# JM_Logics_I2C_SMD_Adapter_v0_1.net
KiCad netlist of a schematic drawn in EAGLE
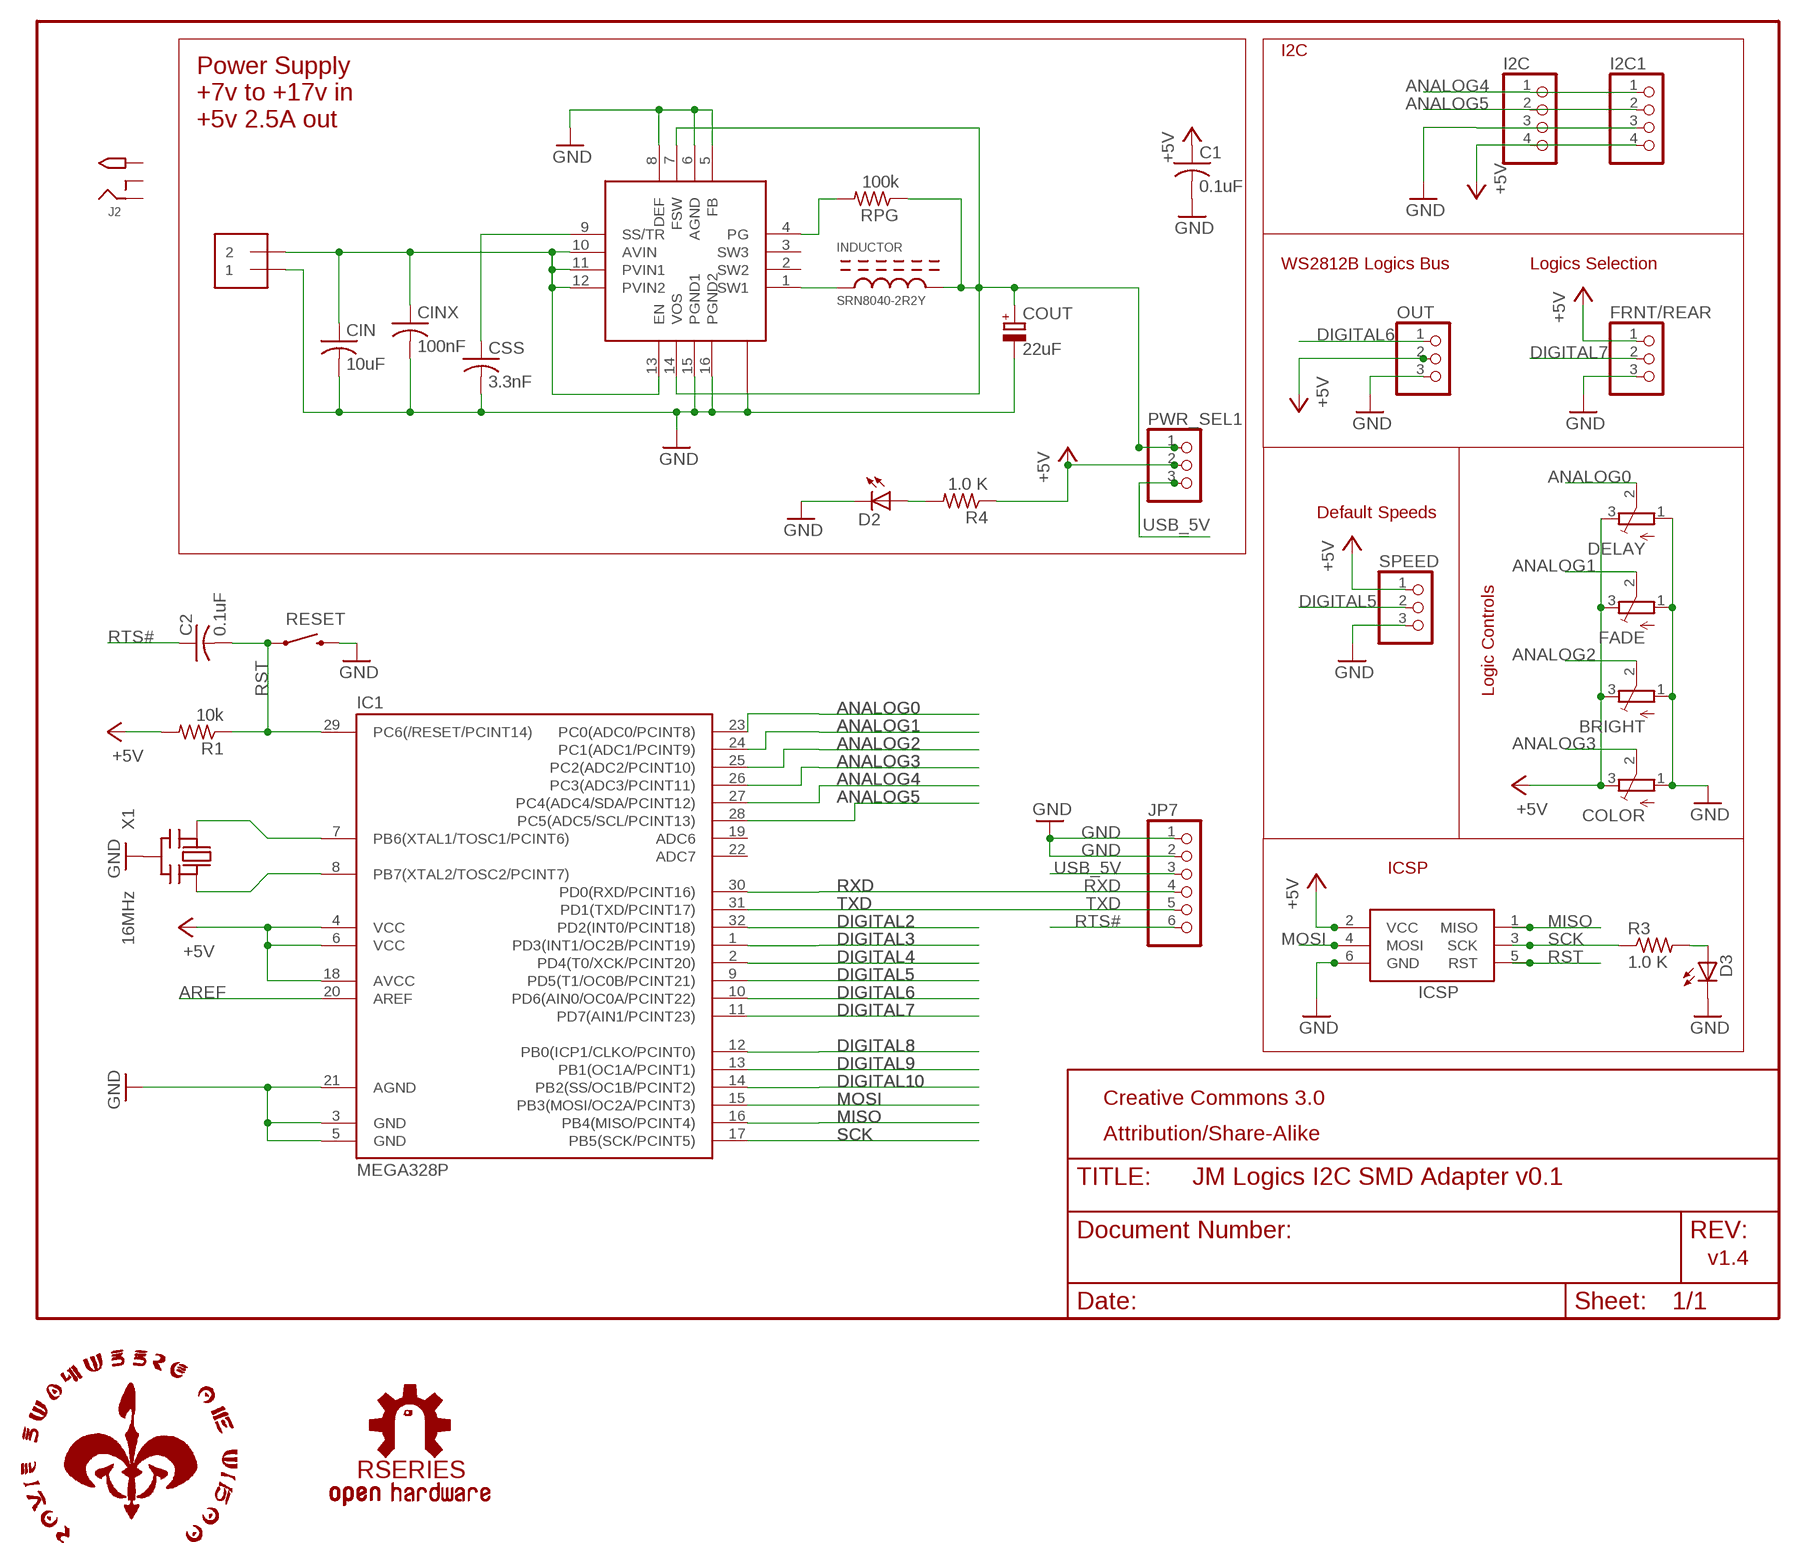
[diagram p0: schematic, sheet 1]

(export (version "E")
  (design (tool "Eeschema 10.0.6"))
  (components
    (comp (ref "BRIGHT")
      (value "TRIMPOTTC33X")
      (footprint "eagle-import:TC33X")
      (libsource (lib "eagle-import") (part "TRIMPOTTC33X"))
    )
    (comp (ref "C1")
      (value "0.1uF")
      (footprint "eagle-import:C1206K")
      (libsource (lib "eagle-import") (part "minimidi_C-USC1206K"))
    )
    (comp (ref "C2")
      (value "0.1uF")
      (footprint "eagle-import:C0805K")
      (libsource (lib "eagle-import") (part "C-USC0805K"))
    )
    (comp (ref "CIN")
      (value "10uF")
      (footprint "eagle-import:C0805K")
      (libsource (lib "eagle-import") (part "C-USC0805K"))
    )
    (comp (ref "CINX")
      (value "100nF")
      (footprint "eagle-import:C0805K")
      (libsource (lib "eagle-import") (part "C-USC0805K"))
    )
    (comp (ref "COLOR")
      (value "TRIMPOTTC33X")
      (footprint "eagle-import:TC33X")
      (libsource (lib "eagle-import") (part "TRIMPOTTC33X"))
    )
    (comp (ref "COUT")
      (value "22uF")
      (footprint "eagle-import:CASE_B")
      (libsource (lib "eagle-import") (part "CAPACITOR_POL-CASE_B"))
    )
    (comp (ref "CSS")
      (value "3.3nF")
      (footprint "eagle-import:C0805K")
      (libsource (lib "eagle-import") (part "C-USC0805K"))
    )
    (comp (ref "D2")
      (value "LEDCHIPLED_1206")
      (footprint "eagle-import:CHIPLED_1206")
      (libsource (lib "eagle-import") (part "LEDCHIPLED_1206"))
    )
    (comp (ref "D3")
      (value "Green")
      (footprint "eagle-import:CHIPLED_1206")
      (libsource (lib "eagle-import") (part "LEDCHIPLED_1206"))
    )
    (comp (ref "DELAY")
      (value "TRIMPOTTC33X")
      (footprint "eagle-import:TC33X")
      (libsource (lib "eagle-import") (part "TRIMPOTTC33X"))
    )
    (comp (ref "EXT.PWR")
      (value "1X2-3.5MM")
      (footprint "eagle-import:1X2-3.5MM")
      (libsource (lib "eagle-import") (part "1X2-3.5MM"))
    )
    (comp (ref "FADE")
      (value "TRIMPOTTC33X")
      (footprint "eagle-import:TC33X")
      (libsource (lib "eagle-import") (part "TRIMPOTTC33X"))
    )
    (comp (ref "FRNT/REAR")
      (value "PINHD-1X3")
      (footprint "eagle-import:1X03")
      (libsource (lib "eagle-import") (part "PINHD-1X3"))
    )
    (comp (ref "I2C")
      (value "PINHD-1X4CB")
      (footprint "eagle-import:1X04-CB")
      (libsource (lib "eagle-import") (part "PINHD-1X4CB"))
    )
    (comp (ref "I2C1")
      (value "PINHD-1X4CB")
      (footprint "eagle-import:1X04-CB")
      (libsource (lib "eagle-import") (part "PINHD-1X4CB"))
    )
    (comp (ref "IC1")
      (value "MEGA328P")
      (footprint "eagle-import:TQFP32-08")
      (libsource (lib "eagle-import") (part "MEGA48/88/168-AU"))
    )
    (comp (ref "ICSP")
      (value "AVRISP-6")
      (footprint "eagle-import:AVRISP")
      (libsource (lib "eagle-import") (part "AVRISP-6"))
    )
    (comp (ref "INDUCTOR")
      (value "SRN8040-2R2Y")
      (footprint "eagle-import:SRN8040")
      (libsource (lib "eagle-import") (part "SRN8040"))
    )
    (comp (ref "J2")
      (value "2.1MMJACK")
      (footprint "eagle-import:PJ-102A")
      (libsource (lib "eagle-import") (part "2.1MMJACK"))
    )
    (comp (ref "JP7")
      (value "PINHD-1X6CLEAN")
      (footprint "eagle-import:1X06-CLEAN")
      (libsource (lib "eagle-import") (part "PINHD-1X6CLEAN"))
    )
    (comp (ref "OUT")
      (value "PINHD-1X3")
      (footprint "eagle-import:1X03")
      (libsource (lib "eagle-import") (part "PINHD-1X3"))
    )
    (comp (ref "PWR_SEL1")
      (value "PINHD-1X3")
      (footprint "eagle-import:1X03")
      (libsource (lib "eagle-import") (part "PINHD-1X3"))
    )
    (comp (ref "R1")
      (value "10k")
      (footprint "eagle-import:R0805")
      (libsource (lib "eagle-import") (part "R-US_R0805"))
    )
    (comp (ref "R3")
      (value "1.0 K")
      (footprint "eagle-import:M1206")
      (libsource (lib "eagle-import") (part "minimidi_R-US_M1206"))
    )
    (comp (ref "R4")
      (value "1.0 K")
      (footprint "eagle-import:M1206")
      (libsource (lib "eagle-import") (part "minimidi_R-US_M1206"))
    )
    (comp (ref "REG")
      (value "TPS62133")
      (footprint "eagle-import:TPS6213X")
      (libsource (lib "eagle-import") (part "TPS6213X"))
    )
    (comp (ref "RESET")
      (value "SWITCH-MOMENTARY-2SMD")
      (footprint "eagle-import:TACTILE_SWITCH_SMD")
      (libsource (lib "eagle-import") (part "SWITCH-MOMENTARY-2SMD"))
    )
    (comp (ref "RPG")
      (value "100k")
      (footprint "eagle-import:R0805")
      (libsource (lib "eagle-import") (part "R-US_R0805"))
    )
    (comp (ref "SPEED")
      (value "PINHD-1X3")
      (footprint "eagle-import:1X03")
      (libsource (lib "eagle-import") (part "PINHD-1X3"))
    )
    (comp (ref "U$1")
      (value "ROYAL-ENGINEERS-OF-NABOOSMALL")
      (footprint "eagle-import:ROYAL-ENGINEERS-OF-NABOO-SMALL")
      (libsource (lib "eagle-import") (part "ROYAL-ENGINEERS-OF-NABOOSMALL"))
    )
    (comp (ref "U$2")
      (value "RSERIES-OSHW-LOGOMEDIUM")
      (footprint "eagle-import:RSERIES-OSHW-LOGO-MEDIUM")
      (libsource (lib "eagle-import") (part "RSERIES-OSHW-LOGOMEDIUM"))
    )
    (comp (ref "X1")
      (value "16MHz")
      (footprint "eagle-import:CERM_OSC")
      (libsource (lib "eagle-import") (part "CERMOSCILL"))
    )
  )
  (nets
    (net (code "1") (name "+5V") (class "Default")
      (node (ref "BRIGHT") (pin "3") (pinfunction "E_3") (pintype "passive"))
      (node (ref "C1") (pin "1") (pinfunction "1_1") (pintype "passive"))
      (node (ref "COLOR") (pin "3") (pinfunction "E_3") (pintype "passive"))
      (node (ref "DELAY") (pin "3") (pinfunction "E_3") (pintype "passive"))
      (node (ref "FADE") (pin "3") (pinfunction "E_3") (pintype "passive"))
      (node (ref "FRNT/REAR") (pin "1") (pinfunction "1_1") (pintype "passive"))
      (node (ref "I2C") (pin "4") (pinfunction "4_4") (pintype "passive"))
      (node (ref "I2C1") (pin "4") (pinfunction "4_4") (pintype "passive"))
      (node (ref "IC1") (pin "18") (pinfunction "AVCC_18") (pintype "passive"))
      (node (ref "IC1") (pin "4") (pinfunction "VCC_4") (pintype "power_in"))
      (node (ref "IC1") (pin "6") (pinfunction "VCC_6") (pintype "power_in"))
      (node (ref "ICSP") (pin "2") (pinfunction "VCC_2") (pintype "power_in"))
      (node (ref "OUT") (pin "2") (pinfunction "2_2") (pintype "passive"))
      (node (ref "PWR_SEL1") (pin "2") (pinfunction "2_2") (pintype "passive"))
      (node (ref "R1") (pin "2") (pinfunction "2_2") (pintype "passive"))
      (node (ref "R4") (pin "1") (pinfunction "1_1") (pintype "passive"))
      (node (ref "SPEED") (pin "1") (pinfunction "1_1") (pintype "passive"))
    )
    (net (code "2") (name "/ANALOG0") (class "Default")
      (node (ref "DELAY") (pin "2") (pinfunction "S_2") (pintype "passive"))
      (node (ref "IC1") (pin "23") (pinfunction "PC0(ADC0/PCINT8)_23") (pintype "bidirectional"))
    )
    (net (code "3") (name "/ANALOG1") (class "Default")
      (node (ref "FADE") (pin "2") (pinfunction "S_2") (pintype "passive"))
      (node (ref "IC1") (pin "24") (pinfunction "PC1(ADC1/PCINT9)_24") (pintype "bidirectional"))
    )
    (net (code "4") (name "/ANALOG2") (class "Default")
      (node (ref "BRIGHT") (pin "2") (pinfunction "S_2") (pintype "passive"))
      (node (ref "IC1") (pin "25") (pinfunction "PC2(ADC2/PCINT10)_25") (pintype "bidirectional"))
    )
    (net (code "5") (name "/ANALOG3") (class "Default")
      (node (ref "COLOR") (pin "2") (pinfunction "S_2") (pintype "passive"))
      (node (ref "IC1") (pin "26") (pinfunction "PC3(ADC3/PCINT11)_26") (pintype "bidirectional"))
    )
    (net (code "6") (name "/ANALOG4") (class "Default")
      (node (ref "I2C") (pin "1") (pinfunction "1_1") (pintype "passive"))
      (node (ref "I2C1") (pin "1") (pinfunction "1_1") (pintype "passive"))
      (node (ref "IC1") (pin "27") (pinfunction "PC4(ADC4/SDA/PCINT12)_27") (pintype "bidirectional"))
    )
    (net (code "7") (name "/ANALOG5") (class "Default")
      (node (ref "I2C") (pin "2") (pinfunction "2_2") (pintype "passive"))
      (node (ref "I2C1") (pin "2") (pinfunction "2_2") (pintype "passive"))
      (node (ref "IC1") (pin "28") (pinfunction "PC5(ADC5/SCL/PCINT13)_28") (pintype "bidirectional"))
    )
    (net (code "8") (name "/AREF") (class "Default")
      (node (ref "IC1") (pin "20") (pinfunction "AREF_20") (pintype "passive"))
    )
    (net (code "9") (name "/DIGITAL2") (class "Default")
      (node (ref "IC1") (pin "32") (pinfunction "PD2(INT0/PCINT18)_32") (pintype "bidirectional"))
    )
    (net (code "10") (name "/DIGITAL3") (class "Default")
      (node (ref "IC1") (pin "1") (pinfunction "PD3(INT1/OC2B/PCINT19)_1") (pintype "bidirectional"))
    )
    (net (code "11") (name "/DIGITAL4") (class "Default")
      (node (ref "IC1") (pin "2") (pinfunction "PD4(T0/XCK/PCINT20)_2") (pintype "bidirectional"))
    )
    (net (code "12") (name "/DIGITAL5") (class "Default")
      (node (ref "IC1") (pin "9") (pinfunction "PD5(T1/OC0B/PCINT21)_9") (pintype "bidirectional"))
      (node (ref "SPEED") (pin "2") (pinfunction "2_2") (pintype "passive"))
    )
    (net (code "13") (name "/DIGITAL6") (class "Default")
      (node (ref "IC1") (pin "10") (pinfunction "PD6(AIN0/OC0A/PCINT22)_10") (pintype "bidirectional"))
      (node (ref "OUT") (pin "1") (pinfunction "1_1") (pintype "passive"))
    )
    (net (code "14") (name "/DIGITAL7") (class "Default")
      (node (ref "FRNT/REAR") (pin "2") (pinfunction "2_2") (pintype "passive"))
      (node (ref "IC1") (pin "11") (pinfunction "PD7(AIN1/PCINT23)_11") (pintype "bidirectional"))
    )
    (net (code "15") (name "/DIGITAL8") (class "Default")
      (node (ref "IC1") (pin "12") (pinfunction "PB0(ICP1/CLKO/PCINT0)_12") (pintype "bidirectional"))
    )
    (net (code "16") (name "/DIGITAL9") (class "Default")
      (node (ref "IC1") (pin "13") (pinfunction "PB1(OC1A/PCINT1)_13") (pintype "bidirectional"))
    )
    (net (code "17") (name "/DIGITAL10") (class "Default")
      (node (ref "IC1") (pin "14") (pinfunction "PB2(SS/OC1B/PCINT2)_14") (pintype "bidirectional"))
    )
    (net (code "18") (name "/MISO") (class "Default")
      (node (ref "IC1") (pin "16") (pinfunction "PB4(MISO/PCINT4)_16") (pintype "bidirectional"))
      (node (ref "ICSP") (pin "1") (pinfunction "MISO_1") (pintype "input"))
    )
    (net (code "19") (name "/MOSI") (class "Default")
      (node (ref "IC1") (pin "15") (pinfunction "PB3(MOSI/OC2A/PCINT3)_15") (pintype "bidirectional"))
      (node (ref "ICSP") (pin "4") (pinfunction "MOSI_4") (pintype "output"))
    )
    (net (code "20") (name "/RST") (class "Default")
      (node (ref "C2") (pin "2") (pinfunction "2_2") (pintype "passive"))
      (node (ref "IC1") (pin "29") (pinfunction "PC6(/RESET/PCINT14)_29") (pintype "bidirectional"))
      (node (ref "ICSP") (pin "5") (pinfunction "RST_5") (pintype "output"))
      (node (ref "R1") (pin "1") (pinfunction "1_1") (pintype "passive"))
      (node (ref "RESET") (pin "1") (pinfunction "1_1") (pintype "passive"))
    )
    (net (code "21") (name "/RTS#") (class "Default")
      (node (ref "C2") (pin "1") (pinfunction "1_1") (pintype "passive"))
      (node (ref "JP7") (pin "6") (pinfunction "6_6") (pintype "passive"))
    )
    (net (code "22") (name "/RXD") (class "Default")
      (node (ref "IC1") (pin "30") (pinfunction "PD0(RXD/PCINT16)_30") (pintype "bidirectional"))
      (node (ref "JP7") (pin "4") (pinfunction "4_4") (pintype "passive"))
    )
    (net (code "23") (name "/SCK") (class "Default")
      (node (ref "IC1") (pin "17") (pinfunction "PB5(SCK/PCINT5)_17") (pintype "bidirectional"))
      (node (ref "ICSP") (pin "3") (pinfunction "SCK_3") (pintype "output"))
      (node (ref "R3") (pin "1") (pinfunction "1_1") (pintype "passive"))
    )
    (net (code "24") (name "/TXD") (class "Default")
      (node (ref "IC1") (pin "31") (pinfunction "PD1(TXD/PCINT17)_31") (pintype "bidirectional"))
      (node (ref "JP7") (pin "5") (pinfunction "5_5") (pintype "passive"))
    )
    (net (code "25") (name "/USB_5V") (class "Default")
      (node (ref "JP7") (pin "3") (pinfunction "3_3") (pintype "passive"))
      (node (ref "PWR_SEL1") (pin "3") (pinfunction "3_3") (pintype "passive"))
    )
    (net (code "26") (name "GND") (class "Default")
      (node (ref "BRIGHT") (pin "1") (pinfunction "A_1") (pintype "passive"))
      (node (ref "C1") (pin "2") (pinfunction "2_2") (pintype "passive"))
      (node (ref "CIN") (pin "2") (pinfunction "2_2") (pintype "passive"))
      (node (ref "CINX") (pin "2") (pinfunction "2_2") (pintype "passive"))
      (node (ref "COLOR") (pin "1") (pinfunction "A_1") (pintype "passive"))
      (node (ref "COUT") (pin "-") (pinfunction "-_-") (pintype "passive"))
      (node (ref "CSS") (pin "2") (pinfunction "2_2") (pintype "passive"))
      (node (ref "D2") (pin "C") (pinfunction "C_C") (pintype "passive"))
      (node (ref "D3") (pin "C") (pinfunction "C_C") (pintype "passive"))
      (node (ref "DELAY") (pin "1") (pinfunction "A_1") (pintype "passive"))
      (node (ref "EXT.PWR") (pin "1") (pinfunction "1_1") (pintype "passive"))
      (node (ref "FADE") (pin "1") (pinfunction "A_1") (pintype "passive"))
      (node (ref "FRNT/REAR") (pin "3") (pinfunction "3_3") (pintype "passive"))
      (node (ref "I2C") (pin "3") (pinfunction "3_3") (pintype "passive"))
      (node (ref "I2C1") (pin "3") (pinfunction "3_3") (pintype "passive"))
      (node (ref "IC1") (pin "21") (pinfunction "AGND_21") (pintype "power_in"))
      (node (ref "IC1") (pin "3") (pinfunction "GND_3") (pintype "power_in"))
      (node (ref "IC1") (pin "5") (pinfunction "GND_5") (pintype "power_in"))
      (node (ref "ICSP") (pin "6") (pinfunction "GND_6") (pintype "power_in"))
      (node (ref "JP7") (pin "1") (pinfunction "1_1") (pintype "passive"))
      (node (ref "JP7") (pin "2") (pinfunction "2_2") (pintype "passive"))
      (node (ref "OUT") (pin "3") (pinfunction "3_3") (pintype "passive"))
      (node (ref "REG") (pin "15") (pinfunction "PGND1_15") (pintype "bidirectional"))
      (node (ref "REG") (pin "16") (pinfunction "PGND2_16") (pintype "bidirectional"))
      (node (ref "REG") (pin "17-THERMALPAD") (pinfunction "THERM_17-THERMALPAD") (pintype "bidirectional"))
      (node (ref "REG") (pin "5") (pinfunction "FB_5") (pintype "bidirectional"))
      (node (ref "REG") (pin "6") (pinfunction "AGND_6") (pintype "bidirectional"))
      (node (ref "REG") (pin "8") (pinfunction "DEF_8") (pintype "bidirectional"))
      (node (ref "RESET") (pin "3") (pinfunction "2_3") (pintype "passive"))
      (node (ref "SPEED") (pin "3") (pinfunction "3_3") (pintype "passive"))
      (node (ref "X1") (pin "P$2") (pinfunction "GND_P$2") (pintype "bidirectional"))
    )
    (net (code "27") (name "Net-(D2-PadA)") (class "Default")
      (node (ref "D2") (pin "A") (pinfunction "A_A") (pintype "passive"))
      (node (ref "R4") (pin "2") (pinfunction "2_2") (pintype "passive"))
    )
    (net (code "28") (name "Net-(D3-PadA)") (class "Default")
      (node (ref "D3") (pin "A") (pinfunction "A_A") (pintype "passive"))
      (node (ref "R3") (pin "2") (pinfunction "2_2") (pintype "passive"))
    )
    (net (code "29") (name "Net-(IC1-PB6(XTAL1{slash}TOSC1{slash}PCINT6))") (class "Default")
      (node (ref "IC1") (pin "7") (pinfunction "PB6(XTAL1/TOSC1/PCINT6)_7") (pintype "bidirectional"))
      (node (ref "X1") (pin "P$1") (pinfunction "IN_P$1") (pintype "bidirectional"))
    )
    (net (code "30") (name "Net-(IC1-PB7(XTAL2{slash}TOSC2{slash}PCINT7))") (class "Default")
      (node (ref "IC1") (pin "8") (pinfunction "PB7(XTAL2/TOSC2/PCINT7)_8") (pintype "bidirectional"))
      (node (ref "X1") (pin "P$3") (pinfunction "OUT_P$3") (pintype "bidirectional"))
    )
    (net (code "31") (name "Net-(INDUCTOR-P1)") (class "Default")
      (node (ref "INDUCTOR") (pin "P$1") (pinfunction "P1_P$1") (pintype "bidirectional"))
      (node (ref "REG") (pin "1") (pinfunction "SW1_1") (pintype "bidirectional"))
    )
    (net (code "32") (name "Net-(INDUCTOR-P2)") (class "Default")
      (node (ref "COUT") (pin "+") (pinfunction "+_+") (pintype "passive"))
      (node (ref "INDUCTOR") (pin "P$2") (pinfunction "P2_P$2") (pintype "bidirectional"))
      (node (ref "PWR_SEL1") (pin "1") (pinfunction "1_1") (pintype "passive"))
      (node (ref "REG") (pin "14") (pinfunction "VOS_14") (pintype "bidirectional"))
      (node (ref "REG") (pin "7") (pinfunction "FSW_7") (pintype "bidirectional"))
      (node (ref "RPG") (pin "1") (pinfunction "1_1") (pintype "passive"))
    )
    (net (code "33") (name "Net-(REG-AVIN)") (class "Default")
      (node (ref "CIN") (pin "1") (pinfunction "1_1") (pintype "passive"))
      (node (ref "CINX") (pin "1") (pinfunction "1_1") (pintype "passive"))
      (node (ref "EXT.PWR") (pin "2") (pinfunction "2_2") (pintype "passive"))
      (node (ref "REG") (pin "10") (pinfunction "AVIN_10") (pintype "bidirectional"))
      (node (ref "REG") (pin "11") (pinfunction "PVIN1_11") (pintype "bidirectional"))
      (node (ref "REG") (pin "12") (pinfunction "PVIN2_12") (pintype "bidirectional"))
      (node (ref "REG") (pin "13") (pinfunction "EN_13") (pintype "bidirectional"))
    )
    (net (code "34") (name "Net-(REG-PG)") (class "Default")
      (node (ref "REG") (pin "4") (pinfunction "PG_4") (pintype "bidirectional"))
      (node (ref "RPG") (pin "2") (pinfunction "2_2") (pintype "passive"))
    )
    (net (code "35") (name "Net-(REG-SS{slash}TR)") (class "Default")
      (node (ref "CSS") (pin "1") (pinfunction "1_1") (pintype "passive"))
      (node (ref "REG") (pin "9") (pinfunction "SS/TR_9") (pintype "bidirectional"))
    )
    (net (code "36") (name "unconnected-(IC1-ADC6-Pad19)") (class "Default")
      (node (ref "IC1") (pin "19") (pinfunction "ADC6_19") (pintype "passive"))
    )
    (net (code "37") (name "unconnected-(IC1-ADC7-Pad22)") (class "Default")
      (node (ref "IC1") (pin "22") (pinfunction "ADC7_22") (pintype "passive"))
    )
    (net (code "38") (name "unconnected-(J2-PadRING)") (class "Default")
      (node (ref "J2") (pin "RING") (pinfunction "RING_RING") (pintype "bidirectional"))
    )
    (net (code "39") (name "unconnected-(J2-PadRING_SW)") (class "Default")
      (node (ref "J2") (pin "RING_SW") (pinfunction "RING_SW_RING_SW") (pintype "bidirectional"))
    )
    (net (code "40") (name "unconnected-(J2-PadTIP)") (class "Default")
      (node (ref "J2") (pin "TIP") (pinfunction "TIP_TIP") (pintype "bidirectional"))
    )
    (net (code "41") (name "unconnected-(REG-SW2-Pad2)") (class "Default")
      (node (ref "REG") (pin "2") (pinfunction "SW2_2") (pintype "bidirectional"))
    )
    (net (code "42") (name "unconnected-(REG-SW3-Pad3)") (class "Default")
      (node (ref "REG") (pin "3") (pinfunction "SW3_3") (pintype "bidirectional"))
    )
  )
)
